# LIC_rack_ZB-00.net
KiCad netlist of a schematic drawn in EAGLE
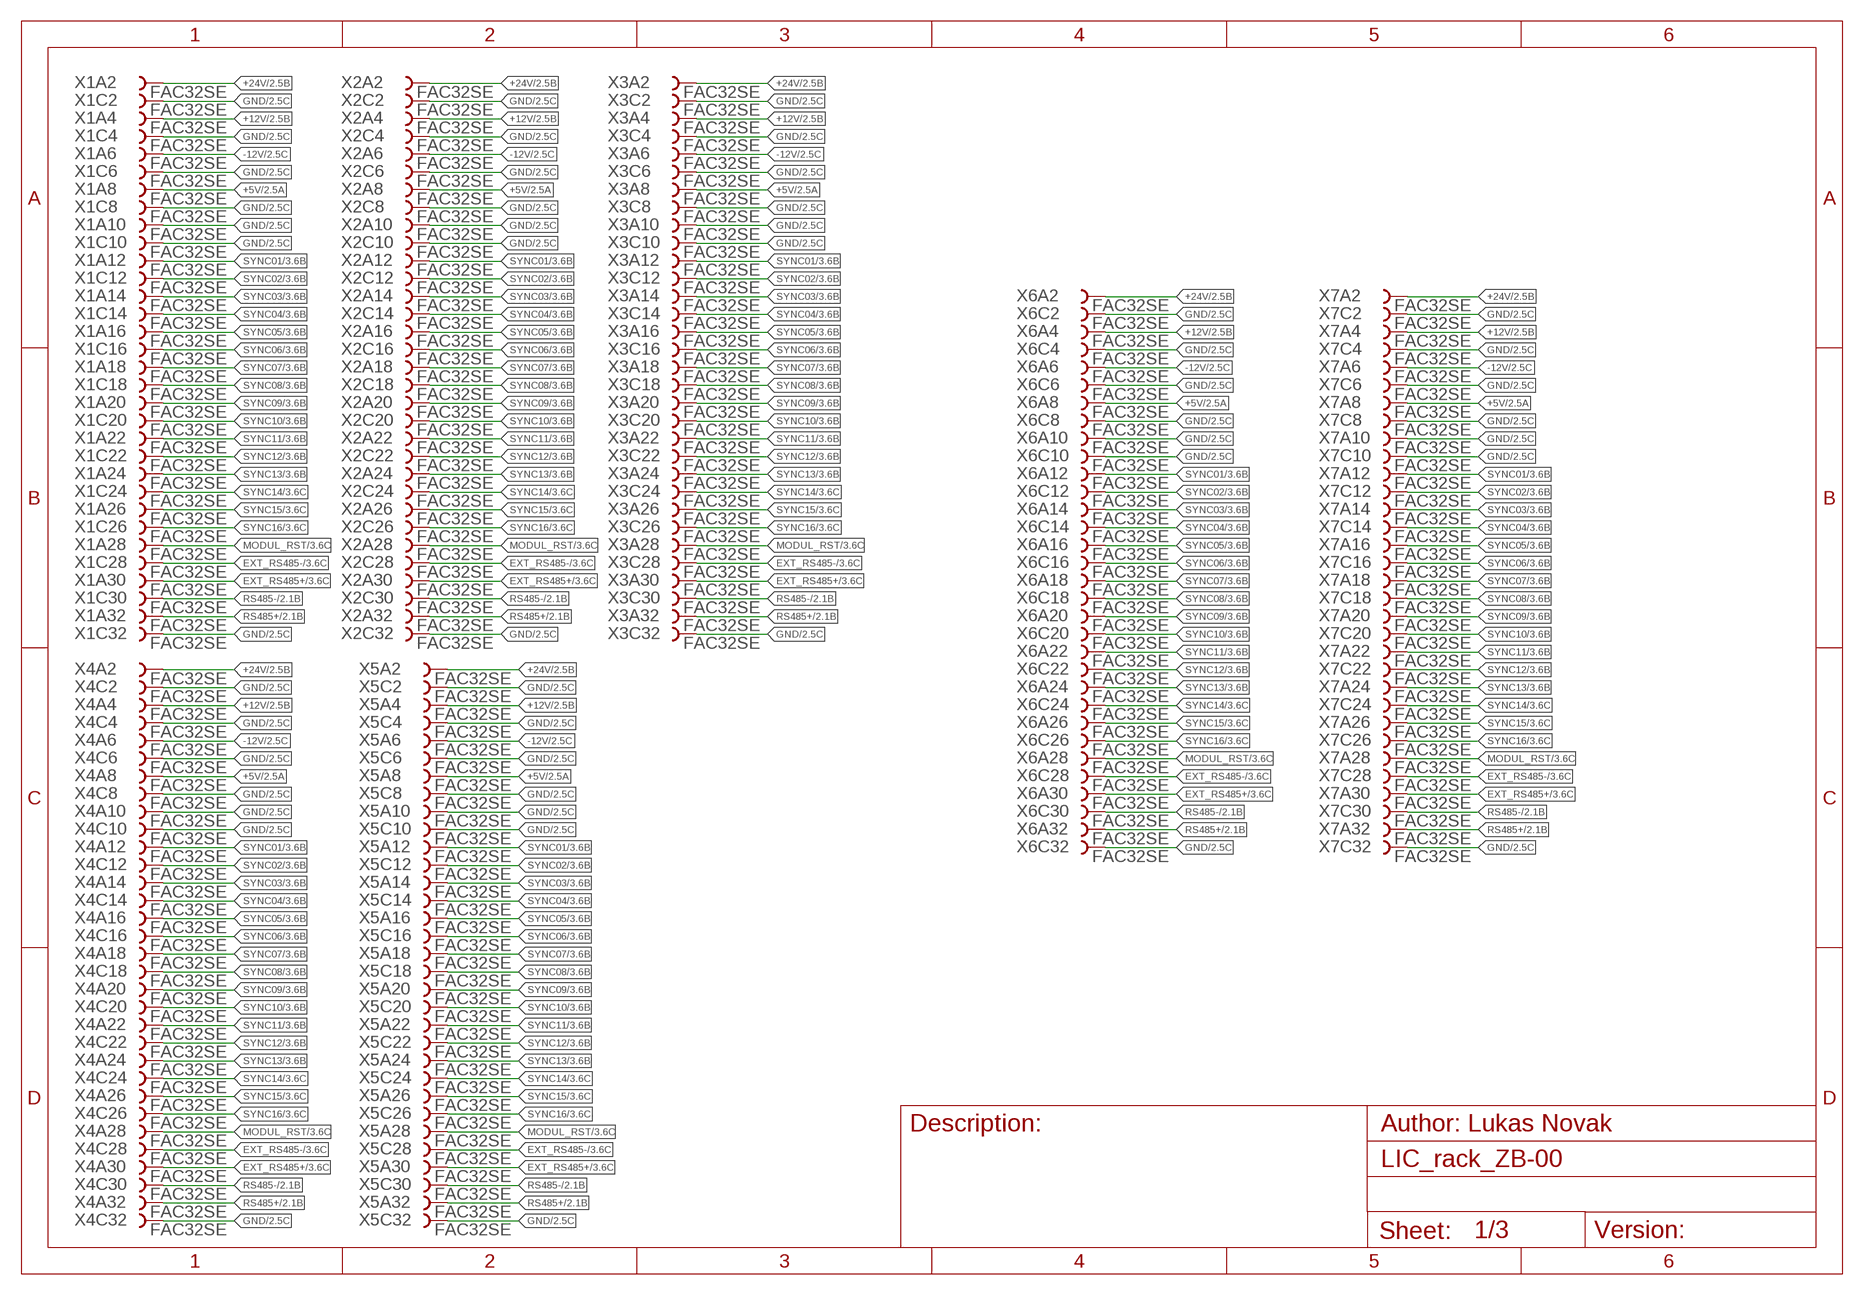
[diagram p0: schematic, sheet 1]
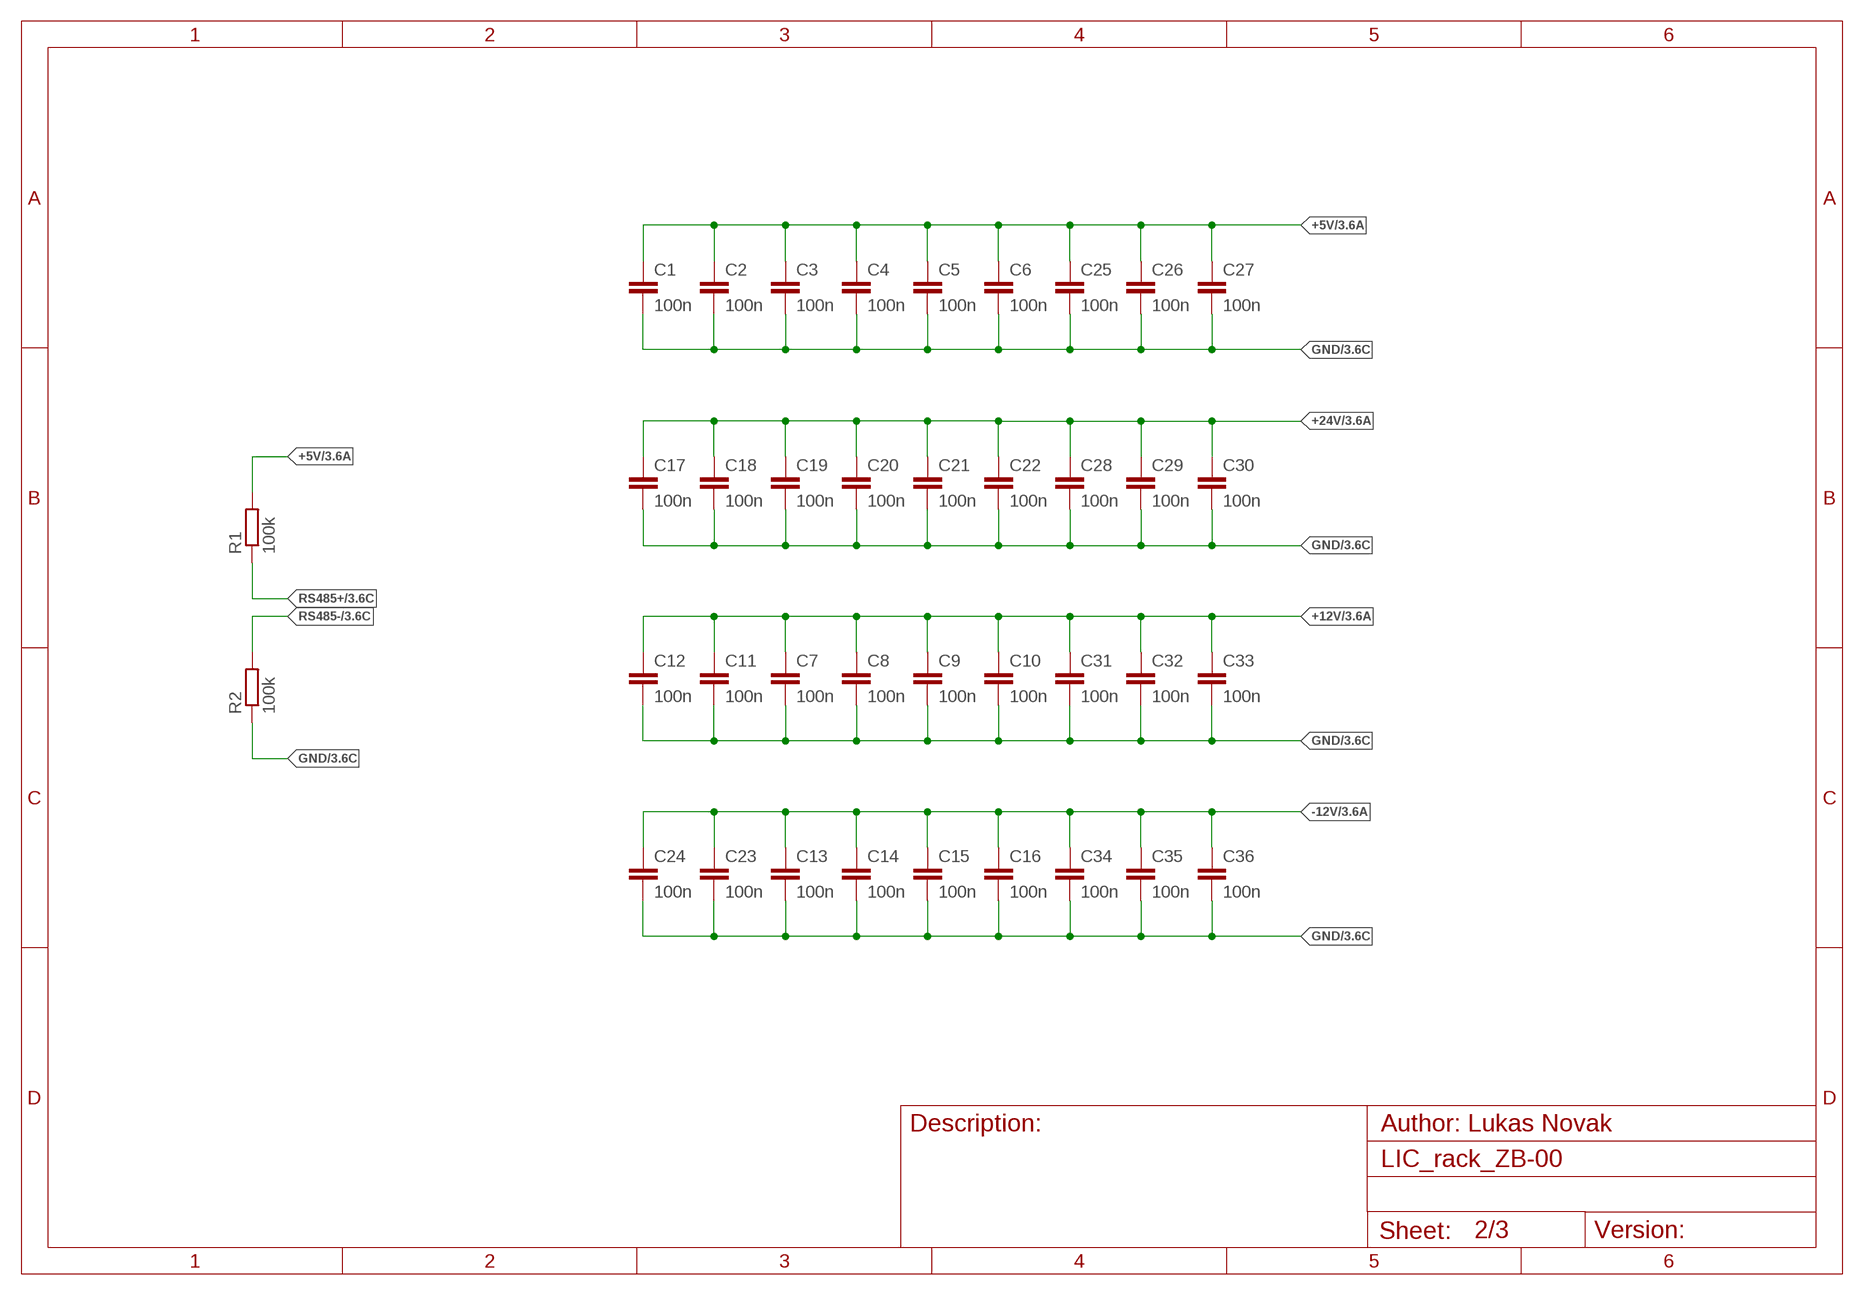
[diagram p1: schematic, sheet 2]
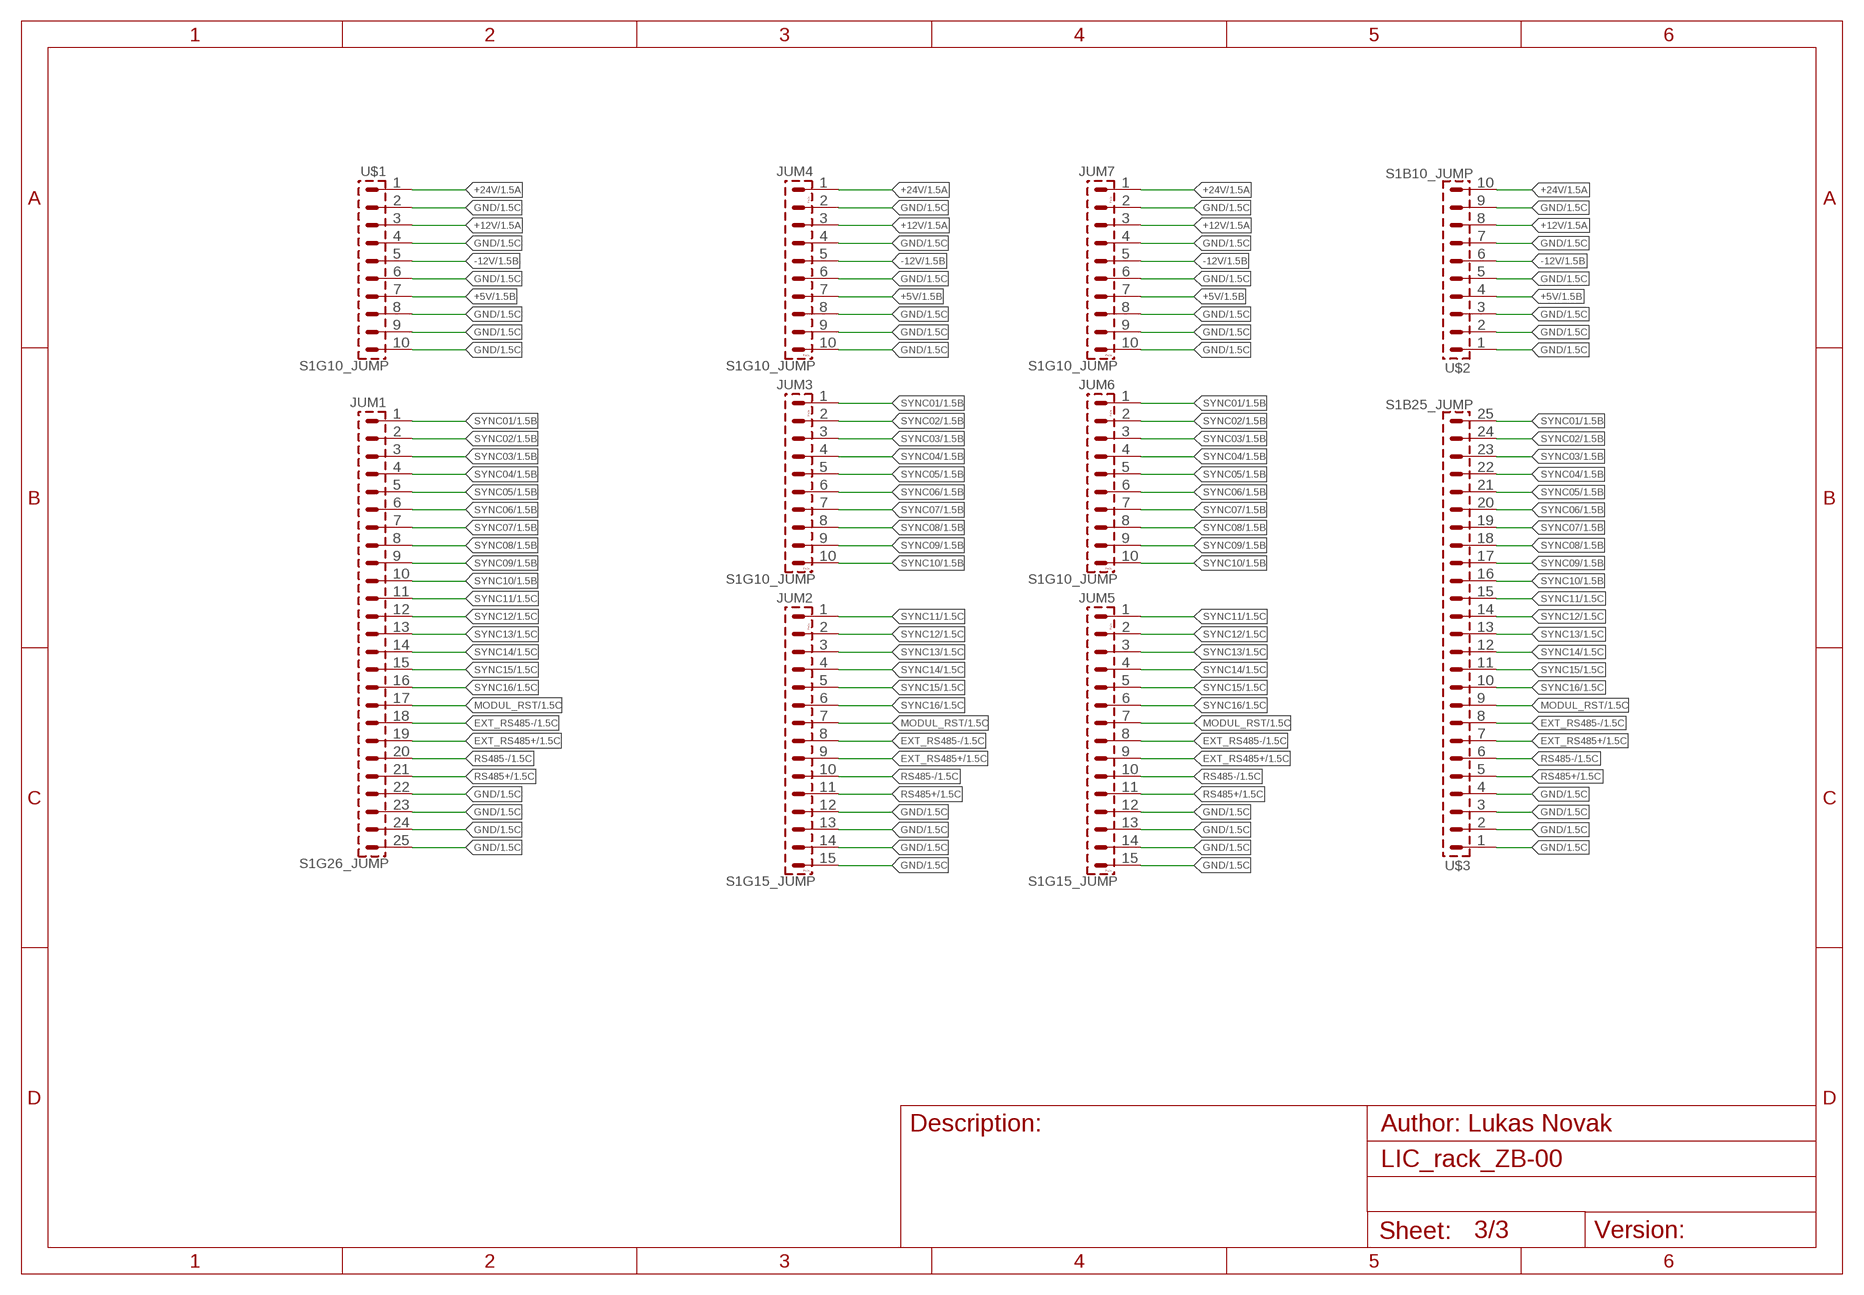
[diagram p2: schematic, sheet 3]

(export (version "E")
  (design (tool "Eeschema 10.0.6"))
  (components
    (comp (ref "JUM1")
      (value "S1G26_JUMP")
      (footprint "eagle-import:S1G26_JU")
      (libsource (lib "eagle-import") (part "S1G26_JUMP"))
    )
    (comp (ref "JUM2")
      (value "S1G15_JUMP")
      (footprint "eagle-import:S1G15_JU")
      (libsource (lib "eagle-import") (part "S1G15_JUMP"))
    )
    (comp (ref "JUM3")
      (value "S1G10_JUMP")
      (footprint "eagle-import:S1G10_JU")
      (libsource (lib "eagle-import") (part "S1G10_JUMP"))
    )
    (comp (ref "JUM4")
      (value "S1G10_JUMP")
      (footprint "eagle-import:S1G10_JU")
      (libsource (lib "eagle-import") (part "S1G10_JUMP"))
    )
    (comp (ref "JUM5")
      (value "S1G15_JUMP")
      (footprint "eagle-import:S1G15_JU")
      (libsource (lib "eagle-import") (part "S1G15_JUMP"))
    )
    (comp (ref "JUM6")
      (value "S1G10_JUMP")
      (footprint "eagle-import:S1G10_JU")
      (libsource (lib "eagle-import") (part "S1G10_JUMP"))
    )
    (comp (ref "JUM7")
      (value "S1G10_JUMP")
      (footprint "eagle-import:S1G10_JU")
      (libsource (lib "eagle-import") (part "S1G10_JUMP"))
    )
    (comp (ref "U$1")
      (value "S1G10_JUMP")
      (footprint "eagle-import:S1G6_JU")
      (libsource (lib "eagle-import") (part "LIC_ALL-00_S1G10_JUMP"))
    )
    (comp (ref "U$2")
      (value "S1B10_JUMP")
      (footprint "eagle-import:S1B10_JU")
      (libsource (lib "eagle-import") (part "S1B10_JUMP"))
    )
    (comp (ref "U$3")
      (value "S1B25_JUMP")
      (footprint "eagle-import:S1B26_JU")
      (libsource (lib "eagle-import") (part "S1B25_JUMP"))
    )
    (comp (ref "X1")
      (value "FAC32SE")
      (footprint "eagle-import:FAC32S")
      (libsource (lib "eagle-import") (part "FAC32SE"))
    )
    (comp (ref "X2")
      (value "FAC32SE")
      (footprint "eagle-import:FAC32S")
      (libsource (lib "eagle-import") (part "FAC32SE"))
    )
    (comp (ref "X3")
      (value "FAC32SE")
      (footprint "eagle-import:FAC32S")
      (libsource (lib "eagle-import") (part "FAC32SE"))
    )
    (comp (ref "X4")
      (value "FAC32SE")
      (footprint "eagle-import:FAC32S")
      (libsource (lib "eagle-import") (part "FAC32SE"))
    )
    (comp (ref "X5")
      (value "FAC32SE")
      (footprint "eagle-import:FAC32S")
      (libsource (lib "eagle-import") (part "FAC32SE"))
    )
    (comp (ref "X6")
      (value "FAC32SE")
      (footprint "eagle-import:FAC32S")
      (libsource (lib "eagle-import") (part "FAC32SE"))
    )
    (comp (ref "X7")
      (value "FAC32SE")
      (footprint "eagle-import:FAC32S")
      (libsource (lib "eagle-import") (part "FAC32SE"))
    )
    (comp (ref "C1")
      (value "100n")
      (footprint "eagle-import:C1206")
      (libsource (lib "eagle-import") (part "C-EUC1206"))
    )
    (comp (ref "C2")
      (value "100n")
      (footprint "eagle-import:C1206")
      (libsource (lib "eagle-import") (part "C-EUC1206"))
    )
    (comp (ref "C3")
      (value "100n")
      (footprint "eagle-import:C1206")
      (libsource (lib "eagle-import") (part "C-EUC1206"))
    )
    (comp (ref "C4")
      (value "100n")
      (footprint "eagle-import:C1206")
      (libsource (lib "eagle-import") (part "C-EUC1206"))
    )
    (comp (ref "C5")
      (value "100n")
      (footprint "eagle-import:C1206")
      (libsource (lib "eagle-import") (part "C-EUC1206"))
    )
    (comp (ref "C6")
      (value "100n")
      (footprint "eagle-import:C1206")
      (libsource (lib "eagle-import") (part "C-EUC1206"))
    )
    (comp (ref "C7")
      (value "100n")
      (footprint "eagle-import:C1206")
      (libsource (lib "eagle-import") (part "C-EUC1206"))
    )
    (comp (ref "C8")
      (value "100n")
      (footprint "eagle-import:C1206")
      (libsource (lib "eagle-import") (part "C-EUC1206"))
    )
    (comp (ref "C9")
      (value "100n")
      (footprint "eagle-import:C1206")
      (libsource (lib "eagle-import") (part "C-EUC1206"))
    )
    (comp (ref "C10")
      (value "100n")
      (footprint "eagle-import:C1206")
      (libsource (lib "eagle-import") (part "C-EUC1206"))
    )
    (comp (ref "C11")
      (value "100n")
      (footprint "eagle-import:C1206")
      (libsource (lib "eagle-import") (part "C-EUC1206"))
    )
    (comp (ref "C12")
      (value "100n")
      (footprint "eagle-import:C1206")
      (libsource (lib "eagle-import") (part "C-EUC1206"))
    )
    (comp (ref "C13")
      (value "100n")
      (footprint "eagle-import:C1206")
      (libsource (lib "eagle-import") (part "C-EUC1206"))
    )
    (comp (ref "C14")
      (value "100n")
      (footprint "eagle-import:C1206")
      (libsource (lib "eagle-import") (part "C-EUC1206"))
    )
    (comp (ref "C15")
      (value "100n")
      (footprint "eagle-import:C1206")
      (libsource (lib "eagle-import") (part "C-EUC1206"))
    )
    (comp (ref "C16")
      (value "100n")
      (footprint "eagle-import:C1206")
      (libsource (lib "eagle-import") (part "C-EUC1206"))
    )
    (comp (ref "C17")
      (value "100n")
      (footprint "eagle-import:C1206")
      (libsource (lib "eagle-import") (part "C-EUC1206"))
    )
    (comp (ref "C18")
      (value "100n")
      (footprint "eagle-import:C1206")
      (libsource (lib "eagle-import") (part "C-EUC1206"))
    )
    (comp (ref "C19")
      (value "100n")
      (footprint "eagle-import:C1206")
      (libsource (lib "eagle-import") (part "C-EUC1206"))
    )
    (comp (ref "C20")
      (value "100n")
      (footprint "eagle-import:C1206")
      (libsource (lib "eagle-import") (part "C-EUC1206"))
    )
    (comp (ref "C21")
      (value "100n")
      (footprint "eagle-import:C1206")
      (libsource (lib "eagle-import") (part "C-EUC1206"))
    )
    (comp (ref "C22")
      (value "100n")
      (footprint "eagle-import:C1206")
      (libsource (lib "eagle-import") (part "C-EUC1206"))
    )
    (comp (ref "C23")
      (value "100n")
      (footprint "eagle-import:C1206")
      (libsource (lib "eagle-import") (part "C-EUC1206"))
    )
    (comp (ref "C24")
      (value "100n")
      (footprint "eagle-import:C1206")
      (libsource (lib "eagle-import") (part "C-EUC1206"))
    )
    (comp (ref "C25")
      (value "100n")
      (footprint "eagle-import:C1206")
      (libsource (lib "eagle-import") (part "C-EUC1206"))
    )
    (comp (ref "C26")
      (value "100n")
      (footprint "eagle-import:C1206")
      (libsource (lib "eagle-import") (part "C-EUC1206"))
    )
    (comp (ref "C27")
      (value "100n")
      (footprint "eagle-import:C1206")
      (libsource (lib "eagle-import") (part "C-EUC1206"))
    )
    (comp (ref "C28")
      (value "100n")
      (footprint "eagle-import:C1206")
      (libsource (lib "eagle-import") (part "C-EUC1206"))
    )
    (comp (ref "C29")
      (value "100n")
      (footprint "eagle-import:C1206")
      (libsource (lib "eagle-import") (part "C-EUC1206"))
    )
    (comp (ref "C30")
      (value "100n")
      (footprint "eagle-import:C1206")
      (libsource (lib "eagle-import") (part "C-EUC1206"))
    )
    (comp (ref "C31")
      (value "100n")
      (footprint "eagle-import:C1206")
      (libsource (lib "eagle-import") (part "C-EUC1206"))
    )
    (comp (ref "C32")
      (value "100n")
      (footprint "eagle-import:C1206")
      (libsource (lib "eagle-import") (part "C-EUC1206"))
    )
    (comp (ref "C33")
      (value "100n")
      (footprint "eagle-import:C1206")
      (libsource (lib "eagle-import") (part "C-EUC1206"))
    )
    (comp (ref "C34")
      (value "100n")
      (footprint "eagle-import:C1206")
      (libsource (lib "eagle-import") (part "C-EUC1206"))
    )
    (comp (ref "C35")
      (value "100n")
      (footprint "eagle-import:C1206")
      (libsource (lib "eagle-import") (part "C-EUC1206"))
    )
    (comp (ref "C36")
      (value "100n")
      (footprint "eagle-import:C1206")
      (libsource (lib "eagle-import") (part "C-EUC1206"))
    )
    (comp (ref "R1")
      (value "100k")
      (footprint "eagle-import:R1206")
      (libsource (lib "eagle-import") (part "R-EU_R1206"))
    )
    (comp (ref "R2")
      (value "100k")
      (footprint "eagle-import:R1206")
      (libsource (lib "eagle-import") (part "R-EU_R1206"))
    )
  )
  (nets
    (net (code "1") (name "+5V") (class "Default")
      (node (ref "C1") (pin "1") (pinfunction "1_1") (pintype "passive"))
      (node (ref "C2") (pin "1") (pinfunction "1_1") (pintype "passive"))
      (node (ref "C25") (pin "1") (pinfunction "1_1") (pintype "passive"))
      (node (ref "C26") (pin "1") (pinfunction "1_1") (pintype "passive"))
      (node (ref "C27") (pin "1") (pinfunction "1_1") (pintype "passive"))
      (node (ref "C3") (pin "1") (pinfunction "1_1") (pintype "passive"))
      (node (ref "C4") (pin "1") (pinfunction "1_1") (pintype "passive"))
      (node (ref "C5") (pin "1") (pinfunction "1_1") (pintype "passive"))
      (node (ref "C6") (pin "1") (pinfunction "1_1") (pintype "passive"))
      (node (ref "JUM4") (pin "7") (pinfunction "7_7") (pintype "passive"))
      (node (ref "JUM7") (pin "7") (pinfunction "7_7") (pintype "passive"))
      (node (ref "R1") (pin "2") (pinfunction "2_2") (pintype "passive"))
      (node (ref "U$1") (pin "7") (pinfunction "7_7") (pintype "passive"))
      (node (ref "U$2") (pin "4") (pinfunction "4_4") (pintype "passive"))
      (node (ref "X1") (pin "A8") (pinfunction "B_A8") (pintype "passive"))
      (node (ref "X2") (pin "A8") (pinfunction "B_A8") (pintype "passive"))
      (node (ref "X3") (pin "A8") (pinfunction "B_A8") (pintype "passive"))
      (node (ref "X4") (pin "A8") (pinfunction "B_A8") (pintype "passive"))
      (node (ref "X5") (pin "A8") (pinfunction "B_A8") (pintype "passive"))
      (node (ref "X6") (pin "A8") (pinfunction "B_A8") (pintype "passive"))
      (node (ref "X7") (pin "A8") (pinfunction "B_A8") (pintype "passive"))
    )
    (net (code "2") (name "+12V") (class "Default")
      (node (ref "C10") (pin "1") (pinfunction "1_1") (pintype "passive"))
      (node (ref "C11") (pin "1") (pinfunction "1_1") (pintype "passive"))
      (node (ref "C12") (pin "1") (pinfunction "1_1") (pintype "passive"))
      (node (ref "C31") (pin "1") (pinfunction "1_1") (pintype "passive"))
      (node (ref "C32") (pin "1") (pinfunction "1_1") (pintype "passive"))
      (node (ref "C33") (pin "1") (pinfunction "1_1") (pintype "passive"))
      (node (ref "C7") (pin "1") (pinfunction "1_1") (pintype "passive"))
      (node (ref "C8") (pin "1") (pinfunction "1_1") (pintype "passive"))
      (node (ref "C9") (pin "1") (pinfunction "1_1") (pintype "passive"))
      (node (ref "JUM4") (pin "3") (pinfunction "3_3") (pintype "passive"))
      (node (ref "JUM7") (pin "3") (pinfunction "3_3") (pintype "passive"))
      (node (ref "U$1") (pin "3") (pinfunction "3_3") (pintype "passive"))
      (node (ref "U$2") (pin "8") (pinfunction "8_8") (pintype "passive"))
      (node (ref "X1") (pin "A4") (pinfunction "B_A4") (pintype "passive"))
      (node (ref "X2") (pin "A4") (pinfunction "B_A4") (pintype "passive"))
      (node (ref "X3") (pin "A4") (pinfunction "B_A4") (pintype "passive"))
      (node (ref "X4") (pin "A4") (pinfunction "B_A4") (pintype "passive"))
      (node (ref "X5") (pin "A4") (pinfunction "B_A4") (pintype "passive"))
      (node (ref "X6") (pin "A4") (pinfunction "B_A4") (pintype "passive"))
      (node (ref "X7") (pin "A4") (pinfunction "B_A4") (pintype "passive"))
    )
    (net (code "3") (name "+24V") (class "Default")
      (node (ref "C17") (pin "1") (pinfunction "1_1") (pintype "passive"))
      (node (ref "C18") (pin "1") (pinfunction "1_1") (pintype "passive"))
      (node (ref "C19") (pin "1") (pinfunction "1_1") (pintype "passive"))
      (node (ref "C20") (pin "1") (pinfunction "1_1") (pintype "passive"))
      (node (ref "C21") (pin "1") (pinfunction "1_1") (pintype "passive"))
      (node (ref "C22") (pin "1") (pinfunction "1_1") (pintype "passive"))
      (node (ref "C28") (pin "1") (pinfunction "1_1") (pintype "passive"))
      (node (ref "C29") (pin "1") (pinfunction "1_1") (pintype "passive"))
      (node (ref "C30") (pin "1") (pinfunction "1_1") (pintype "passive"))
      (node (ref "JUM4") (pin "1") (pinfunction "1_1") (pintype "passive"))
      (node (ref "JUM7") (pin "1") (pinfunction "1_1") (pintype "passive"))
      (node (ref "U$1") (pin "1") (pinfunction "1_1") (pintype "passive"))
      (node (ref "U$2") (pin "10") (pinfunction "10_10") (pintype "passive"))
      (node (ref "X1") (pin "A2") (pinfunction "B_A2") (pintype "passive"))
      (node (ref "X2") (pin "A2") (pinfunction "B_A2") (pintype "passive"))
      (node (ref "X3") (pin "A2") (pinfunction "B_A2") (pintype "passive"))
      (node (ref "X4") (pin "A2") (pinfunction "B_A2") (pintype "passive"))
      (node (ref "X5") (pin "A2") (pinfunction "B_A2") (pintype "passive"))
      (node (ref "X6") (pin "A2") (pinfunction "B_A2") (pintype "passive"))
      (node (ref "X7") (pin "A2") (pinfunction "B_A2") (pintype "passive"))
    )
    (net (code "4") (name "-12V") (class "Default")
      (node (ref "C13") (pin "1") (pinfunction "1_1") (pintype "passive"))
      (node (ref "C14") (pin "1") (pinfunction "1_1") (pintype "passive"))
      (node (ref "C15") (pin "1") (pinfunction "1_1") (pintype "passive"))
      (node (ref "C16") (pin "1") (pinfunction "1_1") (pintype "passive"))
      (node (ref "C23") (pin "1") (pinfunction "1_1") (pintype "passive"))
      (node (ref "C24") (pin "1") (pinfunction "1_1") (pintype "passive"))
      (node (ref "C34") (pin "1") (pinfunction "1_1") (pintype "passive"))
      (node (ref "C35") (pin "1") (pinfunction "1_1") (pintype "passive"))
      (node (ref "C36") (pin "1") (pinfunction "1_1") (pintype "passive"))
      (node (ref "JUM4") (pin "5") (pinfunction "5_5") (pintype "passive"))
      (node (ref "JUM7") (pin "5") (pinfunction "5_5") (pintype "passive"))
      (node (ref "U$1") (pin "5") (pinfunction "5_5") (pintype "passive"))
      (node (ref "U$2") (pin "6") (pinfunction "6_6") (pintype "passive"))
      (node (ref "X1") (pin "A6") (pinfunction "B_A6") (pintype "passive"))
      (node (ref "X2") (pin "A6") (pinfunction "B_A6") (pintype "passive"))
      (node (ref "X3") (pin "A6") (pinfunction "B_A6") (pintype "passive"))
      (node (ref "X4") (pin "A6") (pinfunction "B_A6") (pintype "passive"))
      (node (ref "X5") (pin "A6") (pinfunction "B_A6") (pintype "passive"))
      (node (ref "X6") (pin "A6") (pinfunction "B_A6") (pintype "passive"))
      (node (ref "X7") (pin "A6") (pinfunction "B_A6") (pintype "passive"))
    )
    (net (code "5") (name "EXT_RS485+") (class "Default")
      (node (ref "JUM1") (pin "19") (pinfunction "19_19") (pintype "passive"))
      (node (ref "JUM2") (pin "9") (pinfunction "9_9") (pintype "passive"))
      (node (ref "JUM5") (pin "9") (pinfunction "9_9") (pintype "passive"))
      (node (ref "U$3") (pin "7") (pinfunction "7_7") (pintype "passive"))
      (node (ref "X1") (pin "A30") (pinfunction "B_A30") (pintype "passive"))
      (node (ref "X2") (pin "A30") (pinfunction "B_A30") (pintype "passive"))
      (node (ref "X3") (pin "A30") (pinfunction "B_A30") (pintype "passive"))
      (node (ref "X4") (pin "A30") (pinfunction "B_A30") (pintype "passive"))
      (node (ref "X5") (pin "A30") (pinfunction "B_A30") (pintype "passive"))
      (node (ref "X6") (pin "A30") (pinfunction "B_A30") (pintype "passive"))
      (node (ref "X7") (pin "A30") (pinfunction "B_A30") (pintype "passive"))
    )
    (net (code "6") (name "EXT_RS485-") (class "Default")
      (node (ref "JUM1") (pin "18") (pinfunction "18_18") (pintype "passive"))
      (node (ref "JUM2") (pin "8") (pinfunction "8_8") (pintype "passive"))
      (node (ref "JUM5") (pin "8") (pinfunction "8_8") (pintype "passive"))
      (node (ref "U$3") (pin "8") (pinfunction "8_8") (pintype "passive"))
      (node (ref "X1") (pin "C28") (pinfunction "B_C28") (pintype "passive"))
      (node (ref "X2") (pin "C28") (pinfunction "B_C28") (pintype "passive"))
      (node (ref "X3") (pin "C28") (pinfunction "B_C28") (pintype "passive"))
      (node (ref "X4") (pin "C28") (pinfunction "B_C28") (pintype "passive"))
      (node (ref "X5") (pin "C28") (pinfunction "B_C28") (pintype "passive"))
      (node (ref "X6") (pin "C28") (pinfunction "B_C28") (pintype "passive"))
      (node (ref "X7") (pin "C28") (pinfunction "B_C28") (pintype "passive"))
    )
    (net (code "7") (name "GND") (class "Default")
      (node (ref "C1") (pin "2") (pinfunction "2_2") (pintype "passive"))
      (node (ref "C10") (pin "2") (pinfunction "2_2") (pintype "passive"))
      (node (ref "C11") (pin "2") (pinfunction "2_2") (pintype "passive"))
      (node (ref "C12") (pin "2") (pinfunction "2_2") (pintype "passive"))
      (node (ref "C13") (pin "2") (pinfunction "2_2") (pintype "passive"))
      (node (ref "C14") (pin "2") (pinfunction "2_2") (pintype "passive"))
      (node (ref "C15") (pin "2") (pinfunction "2_2") (pintype "passive"))
      (node (ref "C16") (pin "2") (pinfunction "2_2") (pintype "passive"))
      (node (ref "C17") (pin "2") (pinfunction "2_2") (pintype "passive"))
      (node (ref "C18") (pin "2") (pinfunction "2_2") (pintype "passive"))
      (node (ref "C19") (pin "2") (pinfunction "2_2") (pintype "passive"))
      (node (ref "C2") (pin "2") (pinfunction "2_2") (pintype "passive"))
      (node (ref "C20") (pin "2") (pinfunction "2_2") (pintype "passive"))
      (node (ref "C21") (pin "2") (pinfunction "2_2") (pintype "passive"))
      (node (ref "C22") (pin "2") (pinfunction "2_2") (pintype "passive"))
      (node (ref "C23") (pin "2") (pinfunction "2_2") (pintype "passive"))
      (node (ref "C24") (pin "2") (pinfunction "2_2") (pintype "passive"))
      (node (ref "C25") (pin "2") (pinfunction "2_2") (pintype "passive"))
      (node (ref "C26") (pin "2") (pinfunction "2_2") (pintype "passive"))
      (node (ref "C27") (pin "2") (pinfunction "2_2") (pintype "passive"))
      (node (ref "C28") (pin "2") (pinfunction "2_2") (pintype "passive"))
      (node (ref "C29") (pin "2") (pinfunction "2_2") (pintype "passive"))
      (node (ref "C3") (pin "2") (pinfunction "2_2") (pintype "passive"))
      (node (ref "C30") (pin "2") (pinfunction "2_2") (pintype "passive"))
      (node (ref "C31") (pin "2") (pinfunction "2_2") (pintype "passive"))
      (node (ref "C32") (pin "2") (pinfunction "2_2") (pintype "passive"))
      (node (ref "C33") (pin "2") (pinfunction "2_2") (pintype "passive"))
      (node (ref "C34") (pin "2") (pinfunction "2_2") (pintype "passive"))
      (node (ref "C35") (pin "2") (pinfunction "2_2") (pintype "passive"))
      (node (ref "C36") (pin "2") (pinfunction "2_2") (pintype "passive"))
      (node (ref "C4") (pin "2") (pinfunction "2_2") (pintype "passive"))
      (node (ref "C5") (pin "2") (pinfunction "2_2") (pintype "passive"))
      (node (ref "C6") (pin "2") (pinfunction "2_2") (pintype "passive"))
      (node (ref "C7") (pin "2") (pinfunction "2_2") (pintype "passive"))
      (node (ref "C8") (pin "2") (pinfunction "2_2") (pintype "passive"))
      (node (ref "C9") (pin "2") (pinfunction "2_2") (pintype "passive"))
      (node (ref "JUM1") (pin "22") (pinfunction "22_22") (pintype "passive"))
      (node (ref "JUM1") (pin "23") (pinfunction "23_23") (pintype "passive"))
      (node (ref "JUM1") (pin "24") (pinfunction "24_24") (pintype "passive"))
      (node (ref "JUM1") (pin "25") (pinfunction "25_25") (pintype "passive"))
      (node (ref "JUM2") (pin "12") (pinfunction "12_12") (pintype "passive"))
      (node (ref "JUM2") (pin "13") (pinfunction "13_13") (pintype "passive"))
      (node (ref "JUM2") (pin "14") (pinfunction "14_14") (pintype "passive"))
      (node (ref "JUM2") (pin "15") (pinfunction "15_15") (pintype "passive"))
      (node (ref "JUM4") (pin "10") (pinfunction "10_10") (pintype "passive"))
      (node (ref "JUM4") (pin "2") (pinfunction "2_2") (pintype "passive"))
      (node (ref "JUM4") (pin "4") (pinfunction "4_4") (pintype "passive"))
      (node (ref "JUM4") (pin "6") (pinfunction "6_6") (pintype "passive"))
      (node (ref "JUM4") (pin "8") (pinfunction "8_8") (pintype "passive"))
      (node (ref "JUM4") (pin "9") (pinfunction "9_9") (pintype "passive"))
      (node (ref "JUM5") (pin "12") (pinfunction "12_12") (pintype "passive"))
      (node (ref "JUM5") (pin "13") (pinfunction "13_13") (pintype "passive"))
      (node (ref "JUM5") (pin "14") (pinfunction "14_14") (pintype "passive"))
      (node (ref "JUM5") (pin "15") (pinfunction "15_15") (pintype "passive"))
      (node (ref "JUM7") (pin "10") (pinfunction "10_10") (pintype "passive"))
      (node (ref "JUM7") (pin "2") (pinfunction "2_2") (pintype "passive"))
      (node (ref "JUM7") (pin "4") (pinfunction "4_4") (pintype "passive"))
      (node (ref "JUM7") (pin "6") (pinfunction "6_6") (pintype "passive"))
      (node (ref "JUM7") (pin "8") (pinfunction "8_8") (pintype "passive"))
      (node (ref "JUM7") (pin "9") (pinfunction "9_9") (pintype "passive"))
      (node (ref "R2") (pin "1") (pinfunction "1_1") (pintype "passive"))
      (node (ref "U$1") (pin "10") (pinfunction "10_10") (pintype "passive"))
      (node (ref "U$1") (pin "2") (pinfunction "2_2") (pintype "passive"))
      (node (ref "U$1") (pin "4") (pinfunction "4_4") (pintype "passive"))
      (node (ref "U$1") (pin "6") (pinfunction "6_6") (pintype "passive"))
      (node (ref "U$1") (pin "8") (pinfunction "8_8") (pintype "passive"))
      (node (ref "U$1") (pin "9") (pinfunction "9_9") (pintype "passive"))
      (node (ref "U$2") (pin "1") (pinfunction "1_1") (pintype "passive"))
      (node (ref "U$2") (pin "2") (pinfunction "2_2") (pintype "passive"))
      (node (ref "U$2") (pin "3") (pinfunction "3_3") (pintype "passive"))
      (node (ref "U$2") (pin "5") (pinfunction "5_5") (pintype "passive"))
      (node (ref "U$2") (pin "7") (pinfunction "7_7") (pintype "passive"))
      (node (ref "U$2") (pin "9") (pinfunction "9_9") (pintype "passive"))
      (node (ref "U$3") (pin "1") (pinfunction "1_1") (pintype "passive"))
      (node (ref "U$3") (pin "2") (pinfunction "2_2") (pintype "passive"))
      (node (ref "U$3") (pin "3") (pinfunction "3_3") (pintype "passive"))
      (node (ref "U$3") (pin "4") (pinfunction "4_4") (pintype "passive"))
      (node (ref "X1") (pin "A10") (pinfunction "B_A10") (pintype "passive"))
      (node (ref "X1") (pin "C10") (pinfunction "B_C10") (pintype "passive"))
      (node (ref "X1") (pin "C2") (pinfunction "B_C2") (pintype "passive"))
      (node (ref "X1") (pin "C32") (pinfunction "B_C32") (pintype "passive"))
      (node (ref "X1") (pin "C4") (pinfunction "B_C4") (pintype "passive"))
      (node (ref "X1") (pin "C6") (pinfunction "B_C6") (pintype "passive"))
      (node (ref "X1") (pin "C8") (pinfunction "B_C8") (pintype "passive"))
      (node (ref "X2") (pin "A10") (pinfunction "B_A10") (pintype "passive"))
      (node (ref "X2") (pin "C10") (pinfunction "B_C10") (pintype "passive"))
      (node (ref "X2") (pin "C2") (pinfunction "B_C2") (pintype "passive"))
      (node (ref "X2") (pin "C32") (pinfunction "B_C32") (pintype "passive"))
      (node (ref "X2") (pin "C4") (pinfunction "B_C4") (pintype "passive"))
      (node (ref "X2") (pin "C6") (pinfunction "B_C6") (pintype "passive"))
      (node (ref "X2") (pin "C8") (pinfunction "B_C8") (pintype "passive"))
      (node (ref "X3") (pin "A10") (pinfunction "B_A10") (pintype "passive"))
      (node (ref "X3") (pin "C10") (pinfunction "B_C10") (pintype "passive"))
      (node (ref "X3") (pin "C2") (pinfunction "B_C2") (pintype "passive"))
      (node (ref "X3") (pin "C32") (pinfunction "B_C32") (pintype "passive"))
      (node (ref "X3") (pin "C4") (pinfunction "B_C4") (pintype "passive"))
      (node (ref "X3") (pin "C6") (pinfunction "B_C6") (pintype "passive"))
      (node (ref "X3") (pin "C8") (pinfunction "B_C8") (pintype "passive"))
      (node (ref "X4") (pin "A10") (pinfunction "B_A10") (pintype "passive"))
      (node (ref "X4") (pin "C10") (pinfunction "B_C10") (pintype "passive"))
      (node (ref "X4") (pin "C2") (pinfunction "B_C2") (pintype "passive"))
      (node (ref "X4") (pin "C32") (pinfunction "B_C32") (pintype "passive"))
      (node (ref "X4") (pin "C4") (pinfunction "B_C4") (pintype "passive"))
      (node (ref "X4") (pin "C6") (pinfunction "B_C6") (pintype "passive"))
      (node (ref "X4") (pin "C8") (pinfunction "B_C8") (pintype "passive"))
      (node (ref "X5") (pin "A10") (pinfunction "B_A10") (pintype "passive"))
      (node (ref "X5") (pin "C10") (pinfunction "B_C10") (pintype "passive"))
      (node (ref "X5") (pin "C2") (pinfunction "B_C2") (pintype "passive"))
      (node (ref "X5") (pin "C32") (pinfunction "B_C32") (pintype "passive"))
      (node (ref "X5") (pin "C4") (pinfunction "B_C4") (pintype "passive"))
      (node (ref "X5") (pin "C6") (pinfunction "B_C6") (pintype "passive"))
      (node (ref "X5") (pin "C8") (pinfunction "B_C8") (pintype "passive"))
      (node (ref "X6") (pin "A10") (pinfunction "B_A10") (pintype "passive"))
      (node (ref "X6") (pin "C10") (pinfunction "B_C10") (pintype "passive"))
      (node (ref "X6") (pin "C2") (pinfunction "B_C2") (pintype "passive"))
      (node (ref "X6") (pin "C32") (pinfunction "B_C32") (pintype "passive"))
      (node (ref "X6") (pin "C4") (pinfunction "B_C4") (pintype "passive"))
      (node (ref "X6") (pin "C6") (pinfunction "B_C6") (pintype "passive"))
      (node (ref "X6") (pin "C8") (pinfunction "B_C8") (pintype "passive"))
      (node (ref "X7") (pin "A10") (pinfunction "B_A10") (pintype "passive"))
      (node (ref "X7") (pin "C10") (pinfunction "B_C10") (pintype "passive"))
      (node (ref "X7") (pin "C2") (pinfunction "B_C2") (pintype "passive"))
      (node (ref "X7") (pin "C32") (pinfunction "B_C32") (pintype "passive"))
      (node (ref "X7") (pin "C4") (pinfunction "B_C4") (pintype "passive"))
      (node (ref "X7") (pin "C6") (pinfunction "B_C6") (pintype "passive"))
      (node (ref "X7") (pin "C8") (pinfunction "B_C8") (pintype "passive"))
    )
    (net (code "8") (name "MODUL_RST") (class "Default")
      (node (ref "JUM1") (pin "17") (pinfunction "17_17") (pintype "passive"))
      (node (ref "JUM2") (pin "7") (pinfunction "7_7") (pintype "passive"))
      (node (ref "JUM5") (pin "7") (pinfunction "7_7") (pintype "passive"))
      (node (ref "U$3") (pin "9") (pinfunction "9_9") (pintype "passive"))
      (node (ref "X1") (pin "A28") (pinfunction "B_A28") (pintype "passive"))
      (node (ref "X2") (pin "A28") (pinfunction "B_A28") (pintype "passive"))
      (node (ref "X3") (pin "A28") (pinfunction "B_A28") (pintype "passive"))
      (node (ref "X4") (pin "A28") (pinfunction "B_A28") (pintype "passive"))
      (node (ref "X5") (pin "A28") (pinfunction "B_A28") (pintype "passive"))
      (node (ref "X6") (pin "A28") (pinfunction "B_A28") (pintype "passive"))
      (node (ref "X7") (pin "A28") (pinfunction "B_A28") (pintype "passive"))
    )
    (net (code "9") (name "RS485+") (class "Default")
      (node (ref "JUM1") (pin "21") (pinfunction "21_21") (pintype "passive"))
      (node (ref "JUM2") (pin "11") (pinfunction "11_11") (pintype "passive"))
      (node (ref "JUM5") (pin "11") (pinfunction "11_11") (pintype "passive"))
      (node (ref "R1") (pin "1") (pinfunction "1_1") (pintype "passive"))
      (node (ref "U$3") (pin "5") (pinfunction "5_5") (pintype "passive"))
      (node (ref "X1") (pin "A32") (pinfunction "B_A32") (pintype "passive"))
      (node (ref "X2") (pin "A32") (pinfunction "B_A32") (pintype "passive"))
      (node (ref "X3") (pin "A32") (pinfunction "B_A32") (pintype "passive"))
      (node (ref "X4") (pin "A32") (pinfunction "B_A32") (pintype "passive"))
      (node (ref "X5") (pin "A32") (pinfunction "B_A32") (pintype "passive"))
      (node (ref "X6") (pin "A32") (pinfunction "B_A32") (pintype "passive"))
      (node (ref "X7") (pin "A32") (pinfunction "B_A32") (pintype "passive"))
    )
    (net (code "10") (name "RS485-") (class "Default")
      (node (ref "JUM1") (pin "20") (pinfunction "20_20") (pintype "passive"))
      (node (ref "JUM2") (pin "10") (pinfunction "10_10") (pintype "passive"))
      (node (ref "JUM5") (pin "10") (pinfunction "10_10") (pintype "passive"))
      (node (ref "R2") (pin "2") (pinfunction "2_2") (pintype "passive"))
      (node (ref "U$3") (pin "6") (pinfunction "6_6") (pintype "passive"))
      (node (ref "X1") (pin "C30") (pinfunction "B_C30") (pintype "passive"))
      (node (ref "X2") (pin "C30") (pinfunction "B_C30") (pintype "passive"))
      (node (ref "X3") (pin "C30") (pinfunction "B_C30") (pintype "passive"))
      (node (ref "X4") (pin "C30") (pinfunction "B_C30") (pintype "passive"))
      (node (ref "X5") (pin "C30") (pinfunction "B_C30") (pintype "passive"))
      (node (ref "X6") (pin "C30") (pinfunction "B_C30") (pintype "passive"))
      (node (ref "X7") (pin "C30") (pinfunction "B_C30") (pintype "passive"))
    )
    (net (code "11") (name "SYNC01") (class "Default")
      (node (ref "JUM1") (pin "1") (pinfunction "1_1") (pintype "passive"))
      (node (ref "JUM3") (pin "1") (pinfunction "1_1") (pintype "passive"))
      (node (ref "JUM6") (pin "1") (pinfunction "1_1") (pintype "passive"))
      (node (ref "U$3") (pin "25") (pinfunction "25_25") (pintype "passive"))
      (node (ref "X1") (pin "A12") (pinfunction "B_A12") (pintype "passive"))
      (node (ref "X2") (pin "A12") (pinfunction "B_A12") (pintype "passive"))
      (node (ref "X3") (pin "A12") (pinfunction "B_A12") (pintype "passive"))
      (node (ref "X4") (pin "A12") (pinfunction "B_A12") (pintype "passive"))
      (node (ref "X5") (pin "A12") (pinfunction "B_A12") (pintype "passive"))
      (node (ref "X6") (pin "A12") (pinfunction "B_A12") (pintype "passive"))
      (node (ref "X7") (pin "A12") (pinfunction "B_A12") (pintype "passive"))
    )
    (net (code "12") (name "SYNC02") (class "Default")
      (node (ref "JUM1") (pin "2") (pinfunction "2_2") (pintype "passive"))
      (node (ref "JUM3") (pin "2") (pinfunction "2_2") (pintype "passive"))
      (node (ref "JUM6") (pin "2") (pinfunction "2_2") (pintype "passive"))
      (node (ref "U$3") (pin "24") (pinfunction "24_24") (pintype "passive"))
      (node (ref "X1") (pin "C12") (pinfunction "B_C12") (pintype "passive"))
      (node (ref "X2") (pin "C12") (pinfunction "B_C12") (pintype "passive"))
      (node (ref "X3") (pin "C12") (pinfunction "B_C12") (pintype "passive"))
      (node (ref "X4") (pin "C12") (pinfunction "B_C12") (pintype "passive"))
      (node (ref "X5") (pin "C12") (pinfunction "B_C12") (pintype "passive"))
      (node (ref "X6") (pin "C12") (pinfunction "B_C12") (pintype "passive"))
      (node (ref "X7") (pin "C12") (pinfunction "B_C12") (pintype "passive"))
    )
    (net (code "13") (name "SYNC03") (class "Default")
      (node (ref "JUM1") (pin "3") (pinfunction "3_3") (pintype "passive"))
      (node (ref "JUM3") (pin "3") (pinfunction "3_3") (pintype "passive"))
      (node (ref "JUM6") (pin "3") (pinfunction "3_3") (pintype "passive"))
      (node (ref "U$3") (pin "23") (pinfunction "23_23") (pintype "passive"))
      (node (ref "X1") (pin "A14") (pinfunction "B_A14") (pintype "passive"))
      (node (ref "X2") (pin "A14") (pinfunction "B_A14") (pintype "passive"))
      (node (ref "X3") (pin "A14") (pinfunction "B_A14") (pintype "passive"))
      (node (ref "X4") (pin "A14") (pinfunction "B_A14") (pintype "passive"))
      (node (ref "X5") (pin "A14") (pinfunction "B_A14") (pintype "passive"))
      (node (ref "X6") (pin "A14") (pinfunction "B_A14") (pintype "passive"))
      (node (ref "X7") (pin "A14") (pinfunction "B_A14") (pintype "passive"))
    )
    (net (code "14") (name "SYNC04") (class "Default")
      (node (ref "JUM1") (pin "4") (pinfunction "4_4") (pintype "passive"))
      (node (ref "JUM3") (pin "4") (pinfunction "4_4") (pintype "passive"))
      (node (ref "JUM6") (pin "4") (pinfunction "4_4") (pintype "passive"))
      (node (ref "U$3") (pin "22") (pinfunction "22_22") (pintype "passive"))
      (node (ref "X1") (pin "C14") (pinfunction "B_C14") (pintype "passive"))
      (node (ref "X2") (pin "C14") (pinfunction "B_C14") (pintype "passive"))
      (node (ref "X3") (pin "C14") (pinfunction "B_C14") (pintype "passive"))
      (node (ref "X4") (pin "C14") (pinfunction "B_C14") (pintype "passive"))
      (node (ref "X5") (pin "C14") (pinfunction "B_C14") (pintype "passive"))
      (node (ref "X6") (pin "C14") (pinfunction "B_C14") (pintype "passive"))
      (node (ref "X7") (pin "C14") (pinfunction "B_C14") (pintype "passive"))
    )
    (net (code "15") (name "SYNC05") (class "Default")
      (node (ref "JUM1") (pin "5") (pinfunction "5_5") (pintype "passive"))
      (node (ref "JUM3") (pin "5") (pinfunction "5_5") (pintype "passive"))
      (node (ref "JUM6") (pin "5") (pinfunction "5_5") (pintype "passive"))
      (node (ref "U$3") (pin "21") (pinfunction "21_21") (pintype "passive"))
      (node (ref "X1") (pin "A16") (pinfunction "B_A16") (pintype "passive"))
      (node (ref "X2") (pin "A16") (pinfunction "B_A16") (pintype "passive"))
      (node (ref "X3") (pin "A16") (pinfunction "B_A16") (pintype "passive"))
      (node (ref "X4") (pin "A16") (pinfunction "B_A16") (pintype "passive"))
      (node (ref "X5") (pin "A16") (pinfunction "B_A16") (pintype "passive"))
      (node (ref "X6") (pin "A16") (pinfunction "B_A16") (pintype "passive"))
      (node (ref "X7") (pin "A16") (pinfunction "B_A16") (pintype "passive"))
    )
    (net (code "16") (name "SYNC06") (class "Default")
      (node (ref "JUM1") (pin "6") (pinfunction "6_6") (pintype "passive"))
      (node (ref "JUM3") (pin "6") (pinfunction "6_6") (pintype "passive"))
      (node (ref "JUM6") (pin "6") (pinfunction "6_6") (pintype "passive"))
      (node (ref "U$3") (pin "20") (pinfunction "20_20") (pintype "passive"))
      (node (ref "X1") (pin "C16") (pinfunction "B_C16") (pintype "passive"))
      (node (ref "X2") (pin "C16") (pinfunction "B_C16") (pintype "passive"))
      (node (ref "X3") (pin "C16") (pinfunction "B_C16") (pintype "passive"))
      (node (ref "X4") (pin "C16") (pinfunction "B_C16") (pintype "passive"))
      (node (ref "X5") (pin "C16") (pinfunction "B_C16") (pintype "passive"))
      (node (ref "X6") (pin "C16") (pinfunction "B_C16") (pintype "passive"))
      (node (ref "X7") (pin "C16") (pinfunction "B_C16") (pintype "passive"))
    )
    (net (code "17") (name "SYNC07") (class "Default")
      (node (ref "JUM1") (pin "7") (pinfunction "7_7") (pintype "passive"))
      (node (ref "JUM3") (pin "7") (pinfunction "7_7") (pintype "passive"))
      (node (ref "JUM6") (pin "7") (pinfunction "7_7") (pintype "passive"))
      (node (ref "U$3") (pin "19") (pinfunction "19_19") (pintype "passive"))
      (node (ref "X1") (pin "A18") (pinfunction "B_A18") (pintype "passive"))
      (node (ref "X2") (pin "A18") (pinfunction "B_A18") (pintype "passive"))
      (node (ref "X3") (pin "A18") (pinfunction "B_A18") (pintype "passive"))
      (node (ref "X4") (pin "A18") (pinfunction "B_A18") (pintype "passive"))
      (node (ref "X5") (pin "A18") (pinfunction "B_A18") (pintype "passive"))
      (node (ref "X6") (pin "A18") (pinfunction "B_A18") (pintype "passive"))
      (node (ref "X7") (pin "A18") (pinfunction "B_A18") (pintype "passive"))
    )
    (net (code "18") (name "SYNC08") (class "Default")
      (node (ref "JUM1") (pin "8") (pinfunction "8_8") (pintype "passive"))
      (node (ref "JUM3") (pin "8") (pinfunction "8_8") (pintype "passive"))
      (node (ref "JUM6") (pin "8") (pinfunction "8_8") (pintype "passive"))
      (node (ref "U$3") (pin "18") (pinfunction "18_18") (pintype "passive"))
      (node (ref "X1") (pin "C18") (pinfunction "B_C18") (pintype "passive"))
      (node (ref "X2") (pin "C18") (pinfunction "B_C18") (pintype "passive"))
      (node (ref "X3") (pin "C18") (pinfunction "B_C18") (pintype "passive"))
      (node (ref "X4") (pin "C18") (pinfunction "B_C18") (pintype "passive"))
      (node (ref "X5") (pin "C18") (pinfunction "B_C18") (pintype "passive"))
      (node (ref "X6") (pin "C18") (pinfunction "B_C18") (pintype "passive"))
      (node (ref "X7") (pin "C18") (pinfunction "B_C18") (pintype "passive"))
    )
    (net (code "19") (name "SYNC09") (class "Default")
      (node (ref "JUM1") (pin "9") (pinfunction "9_9") (pintype "passive"))
      (node (ref "JUM3") (pin "9") (pinfunction "9_9") (pintype "passive"))
      (node (ref "JUM6") (pin "9") (pinfunction "9_9") (pintype "passive"))
      (node (ref "U$3") (pin "17") (pinfunction "17_17") (pintype "passive"))
      (node (ref "X1") (pin "A20") (pinfunction "B_A20") (pintype "passive"))
      (node (ref "X2") (pin "A20") (pinfunction "B_A20") (pintype "passive"))
      (node (ref "X3") (pin "A20") (pinfunction "B_A20") (pintype "passive"))
      (node (ref "X4") (pin "A20") (pinfunction "B_A20") (pintype "passive"))
      (node (ref "X5") (pin "A20") (pinfunction "B_A20") (pintype "passive"))
      (node (ref "X6") (pin "A20") (pinfunction "B_A20") (pintype "passive"))
      (node (ref "X7") (pin "A20") (pinfunction "B_A20") (pintype "passive"))
    )
    (net (code "20") (name "SYNC10") (class "Default")
      (node (ref "JUM1") (pin "10") (pinfunction "10_10") (pintype "passive"))
      (node (ref "JUM3") (pin "10") (pinfunction "10_10") (pintype "passive"))
      (node (ref "JUM6") (pin "10") (pinfunction "10_10") (pintype "passive"))
      (node (ref "U$3") (pin "16") (pinfunction "16_16") (pintype "passive"))
      (node (ref "X1") (pin "C20") (pinfunction "B_C20") (pintype "passive"))
      (node (ref "X2") (pin "C20") (pinfunction "B_C20") (pintype "passive"))
      (node (ref "X3") (pin "C20") (pinfunction "B_C20") (pintype "passive"))
      (node (ref "X4") (pin "C20") (pinfunction "B_C20") (pintype "passive"))
      (node (ref "X5") (pin "C20") (pinfunction "B_C20") (pintype "passive"))
      (node (ref "X6") (pin "C20") (pinfunction "B_C20") (pintype "passive"))
      (node (ref "X7") (pin "C20") (pinfunction "B_C20") (pintype "passive"))
    )
    (net (code "21") (name "SYNC11") (class "Default")
      (node (ref "JUM1") (pin "11") (pinfunction "11_11") (pintype "passive"))
      (node (ref "JUM2") (pin "1") (pinfunction "1_1") (pintype "passive"))
      (node (ref "JUM5") (pin "1") (pinfunction "1_1") (pintype "passive"))
      (node (ref "U$3") (pin "15") (pinfunction "15_15") (pintype "passive"))
      (node (ref "X1") (pin "A22") (pinfunction "B_A22") (pintype "passive"))
      (node (ref "X2") (pin "A22") (pinfunction "B_A22") (pintype "passive"))
      (node (ref "X3") (pin "A22") (pinfunction "B_A22") (pintype "passive"))
      (node (ref "X4") (pin "A22") (pinfunction "B_A22") (pintype "passive"))
      (node (ref "X5") (pin "A22") (pinfunction "B_A22") (pintype "passive"))
      (node (ref "X6") (pin "A22") (pinfunction "B_A22") (pintype "passive"))
      (node (ref "X7") (pin "A22") (pinfunction "B_A22") (pintype "passive"))
    )
    (net (code "22") (name "SYNC12") (class "Default")
      (node (ref "JUM1") (pin "12") (pinfunction "12_12") (pintype "passive"))
      (node (ref "JUM2") (pin "2") (pinfunction "2_2") (pintype "passive"))
      (node (ref "JUM5") (pin "2") (pinfunction "2_2") (pintype "passive"))
      (node (ref "U$3") (pin "14") (pinfunction "14_14") (pintype "passive"))
      (node (ref "X1") (pin "C22") (pinfunction "B_C22") (pintype "passive"))
      (node (ref "X2") (pin "C22") (pinfunction "B_C22") (pintype "passive"))
      (node (ref "X3") (pin "C22") (pinfunction "B_C22") (pintype "passive"))
      (node (ref "X4") (pin "C22") (pinfunction "B_C22") (pintype "passive"))
      (node (ref "X5") (pin "C22") (pinfunction "B_C22") (pintype "passive"))
      (node (ref "X6") (pin "C22") (pinfunction "B_C22") (pintype "passive"))
      (node (ref "X7") (pin "C22") (pinfunction "B_C22") (pintype "passive"))
    )
    (net (code "23") (name "SYNC13") (class "Default")
      (node (ref "JUM1") (pin "13") (pinfunction "13_13") (pintype "passive"))
      (node (ref "JUM2") (pin "3") (pinfunction "3_3") (pintype "passive"))
      (node (ref "JUM5") (pin "3") (pinfunction "3_3") (pintype "passive"))
      (node (ref "U$3") (pin "13") (pinfunction "13_13") (pintype "passive"))
      (node (ref "X1") (pin "A24") (pinfunction "B_A24") (pintype "passive"))
      (node (ref "X2") (pin "A24") (pinfunction "B_A24") (pintype "passive"))
      (node (ref "X3") (pin "A24") (pinfunction "B_A24") (pintype "passive"))
      (node (ref "X4") (pin "A24") (pinfunction "B_A24") (pintype "passive"))
      (node (ref "X5") (pin "A24") (pinfunction "B_A24") (pintype "passive"))
      (node (ref "X6") (pin "A24") (pinfunction "B_A24") (pintype "passive"))
      (node (ref "X7") (pin "A24") (pinfunction "B_A24") (pintype "passive"))
    )
    (net (code "24") (name "SYNC14") (class "Default")
      (node (ref "JUM1") (pin "14") (pinfunction "14_14") (pintype "passive"))
      (node (ref "JUM2") (pin "4") (pinfunction "4_4") (pintype "passive"))
      (node (ref "JUM5") (pin "4") (pinfunction "4_4") (pintype "passive"))
      (node (ref "U$3") (pin "12") (pinfunction "12_12") (pintype "passive"))
      (node (ref "X1") (pin "C24") (pinfunction "B_C24") (pintype "passive"))
      (node (ref "X2") (pin "C24") (pinfunction "B_C24") (pintype "passive"))
      (node (ref "X3") (pin "C24") (pinfunction "B_C24") (pintype "passive"))
      (node (ref "X4") (pin "C24") (pinfunction "B_C24") (pintype "passive"))
      (node (ref "X5") (pin "C24") (pinfunction "B_C24") (pintype "passive"))
      (node (ref "X6") (pin "C24") (pinfunction "B_C24") (pintype "passive"))
      (node (ref "X7") (pin "C24") (pinfunction "B_C24") (pintype "passive"))
    )
    (net (code "25") (name "SYNC15") (class "Default")
      (node (ref "JUM1") (pin "15") (pinfunction "15_15") (pintype "passive"))
      (node (ref "JUM2") (pin "5") (pinfunction "5_5") (pintype "passive"))
      (node (ref "JUM5") (pin "5") (pinfunction "5_5") (pintype "passive"))
      (node (ref "U$3") (pin "11") (pinfunction "11_11") (pintype "passive"))
      (node (ref "X1") (pin "A26") (pinfunction "B_A26") (pintype "passive"))
      (node (ref "X2") (pin "A26") (pinfunction "B_A26") (pintype "passive"))
      (node (ref "X3") (pin "A26") (pinfunction "B_A26") (pintype "passive"))
      (node (ref "X4") (pin "A26") (pinfunction "B_A26") (pintype "passive"))
      (node (ref "X5") (pin "A26") (pinfunction "B_A26") (pintype "passive"))
      (node (ref "X6") (pin "A26") (pinfunction "B_A26") (pintype "passive"))
      (node (ref "X7") (pin "A26") (pinfunction "B_A26") (pintype "passive"))
    )
    (net (code "26") (name "SYNC16") (class "Default")
      (node (ref "JUM1") (pin "16") (pinfunction "16_16") (pintype "passive"))
      (node (ref "JUM2") (pin "6") (pinfunction "6_6") (pintype "passive"))
      (node (ref "JUM5") (pin "6") (pinfunction "6_6") (pintype "passive"))
      (node (ref "U$3") (pin "10") (pinfunction "10_10") (pintype "passive"))
      (node (ref "X1") (pin "C26") (pinfunction "B_C26") (pintype "passive"))
      (node (ref "X2") (pin "C26") (pinfunction "B_C26") (pintype "passive"))
      (node (ref "X3") (pin "C26") (pinfunction "B_C26") (pintype "passive"))
      (node (ref "X4") (pin "C26") (pinfunction "B_C26") (pintype "passive"))
      (node (ref "X5") (pin "C26") (pinfunction "B_C26") (pintype "passive"))
      (node (ref "X6") (pin "C26") (pinfunction "B_C26") (pintype "passive"))
      (node (ref "X7") (pin "C26") (pinfunction "B_C26") (pintype "passive"))
    )
  )
)
